# Sheet1.net
KiCad netlist of a schematic drawn in Altium Designer
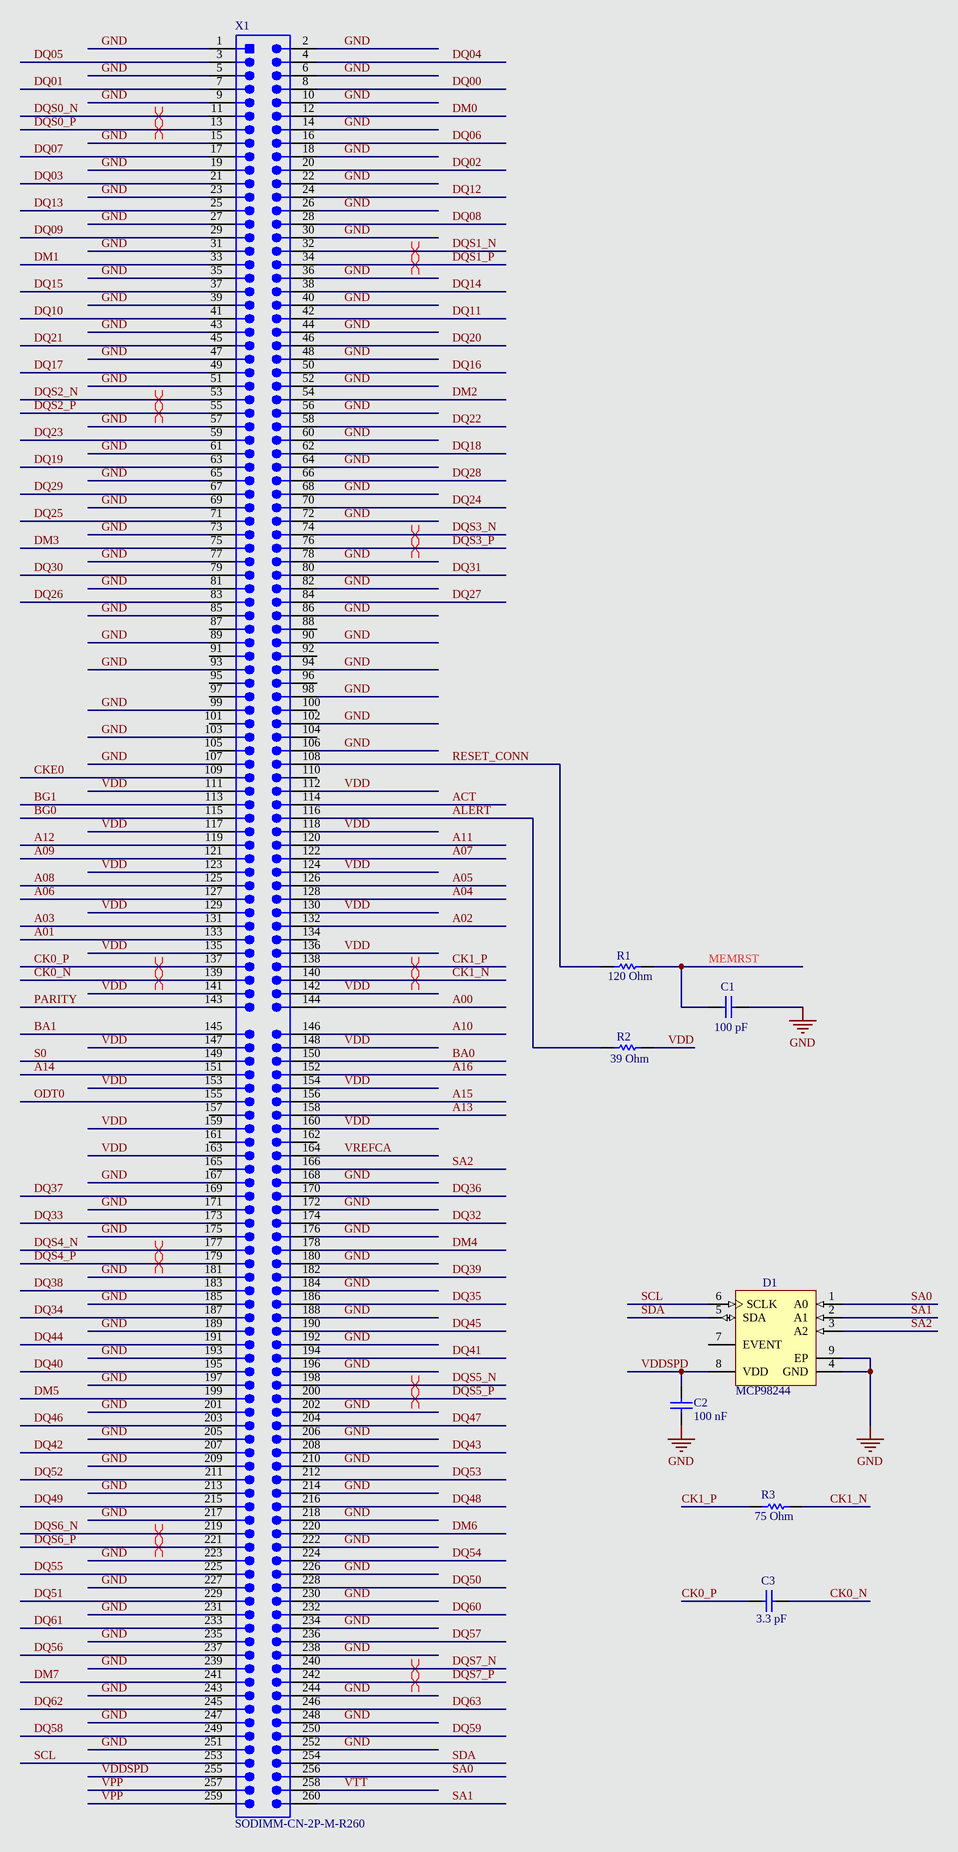
[diagram p0: Sheet1.SchDoc]

(export (version "E")
  (design (tool "Eeschema 10.0.6"))
  (components
    (comp (ref "C1")
      (value "C1005C0G1H101K050BA")
      (footprint "CAPC1005X55X10LL05")
      (description "Chip Capacitor, 100 pF, +/- 10%, 50 V, -55 to 125 degC, 0402 (1005 Metric), RoHS, Tape and Reel")
      (fields (field (name "CAPACITANCE") "100 pF") (field (name "TOLERANCE") "10%"))
      (libsource (lib "Altium Content Vault") (part "CMP-1663-00011-2"))
    )
    (comp (ref "C2")
      (value "C1005X7R1E104M")
      (footprint "CAPC1005X55X10LL05")
      (description "Chip Capacitor, 0.1 uF, +/- 20%, 25 V, -55 to 125 degC, 0402 (1005 Metric), RoHS, Tape and Reel")
      (fields (field (name "TOLERANCE") "20%") (field (name "CAPACITANCE") "100 nF"))
      (libsource (lib "Altium Content Vault") (part "CMP-1663-00009-2"))
    )
    (comp (ref "C3")
      (value "GRM1555C1H3R3CA01D")
      (footprint "CAPC1005X55X25NL5T10")
      (fields (field (name "CAPACITANCE") "3.3 pF"))
      (libsource (lib "Altium Content Vault") (part "CMP-2008-04352-2"))
    )
    (comp (ref "D1")
      (value "MCP98244")
      (footprint "MCHP-TDFN-MNY8_V")
      (libsource (lib "Altium Content Vault") (part "CMP-1721-00006-1"))
    )
    (comp (ref "R1")
      (value "RC0402JR-07120RL")
      (footprint "RESC1005X40X25ML5T10")
      (description "Chip Resistor, 120 Ohm, +/- 5%, 0.063 W, -55 to 155 degC, 0402 (1005 Metric), RoHS, Tape and Reel")
      (fields (field (name "TOLERANCE") "5%") (field (name "RESISTANCE") "120 Ohm"))
      (libsource (lib "Altium Content Vault") (part "CMP-2002-07920-2"))
    )
    (comp (ref "R2")
      (value "RC0402JR-0739RL")
      (footprint "RESC1005X40X25NL5T10")
      (description "Chip Resistor, 39 Ohm, +/- 5%, 0.063 W, -55 to 155 degC, 0402 (1005 Metric), RoHS, Tape and Reel")
      (fields (field (name "TOLERANCE") "5%") (field (name "RESISTANCE") "39 Ohm"))
      (libsource (lib "Altium Content Vault") (part "CMP-2002-07994-2"))
    )
    (comp (ref "R3")
      (value "ERJ-2GEJ750X")
      (footprint "RESC1005X40X25ML05T05")
      (description "Chip Resistor, 75 Ohm, +/- 5%, 100 mW, -55 to 155 degC, 0402 (1005 Metric), RoHS, Tape and Reel")
      (fields
        (field (name "MANUFACTURER") "Basic Passives")
        (field (name "TOLERANCE") "5%")
        (field (name "RESISTANCE") "75 Ohm")
      )
      (libsource (lib "Altium Content Vault") (part "CMP-2002-00578-3"))
    )
    (comp (ref "X1")
      (value "SODIMM-CN-2P-M-R260")
      (footprint "SODIMM-GF-2D-500-1K-S260")
      (description "Golden finger, SODIMM, Dual, Staggered, Pitch 0.5mm, 260-Position")
      (fields (field (name "PUBLISHER") "Altium"))
      (libsource (lib "Altium Content Vault") (part "CMP-0001-00005-1"))
    )
  )
  (nets
    (net (code "1") (name "/A00") (class "Default")
      (node (ref "X1") (pin "144") (pinfunction "144_144") (pintype "passive"))
    )
    (net (code "2") (name "/A01") (class "Default")
      (node (ref "X1") (pin "133") (pinfunction "133_133") (pintype "passive"))
    )
    (net (code "3") (name "/A02") (class "Default")
      (node (ref "X1") (pin "132") (pinfunction "132_132") (pintype "passive"))
    )
    (net (code "4") (name "/A03") (class "Default")
      (node (ref "X1") (pin "131") (pinfunction "131_131") (pintype "passive"))
    )
    (net (code "5") (name "/A04") (class "Default")
      (node (ref "X1") (pin "128") (pinfunction "128_128") (pintype "passive"))
    )
    (net (code "6") (name "/A05") (class "Default")
      (node (ref "X1") (pin "126") (pinfunction "126_126") (pintype "passive"))
    )
    (net (code "7") (name "/A06") (class "Default")
      (node (ref "X1") (pin "127") (pinfunction "127_127") (pintype "passive"))
    )
    (net (code "8") (name "/A07") (class "Default")
      (node (ref "X1") (pin "122") (pinfunction "122_122") (pintype "passive"))
    )
    (net (code "9") (name "/A08") (class "Default")
      (node (ref "X1") (pin "125") (pinfunction "125_125") (pintype "passive"))
    )
    (net (code "10") (name "/A09") (class "Default")
      (node (ref "X1") (pin "121") (pinfunction "121_121") (pintype "passive"))
    )
    (net (code "11") (name "/A10") (class "Default")
      (node (ref "X1") (pin "146") (pinfunction "146_146") (pintype "passive"))
    )
    (net (code "12") (name "/A11") (class "Default")
      (node (ref "X1") (pin "120") (pinfunction "120_120") (pintype "passive"))
    )
    (net (code "13") (name "/A12") (class "Default")
      (node (ref "X1") (pin "119") (pinfunction "119_119") (pintype "passive"))
    )
    (net (code "14") (name "/A13") (class "Default")
      (node (ref "X1") (pin "158") (pinfunction "158_158") (pintype "passive"))
    )
    (net (code "15") (name "/A14") (class "Default")
      (node (ref "X1") (pin "151") (pinfunction "151_151") (pintype "passive"))
    )
    (net (code "16") (name "/A15") (class "Default")
      (node (ref "X1") (pin "156") (pinfunction "156_156") (pintype "passive"))
    )
    (net (code "17") (name "/A16") (class "Default")
      (node (ref "X1") (pin "152") (pinfunction "152_152") (pintype "passive"))
    )
    (net (code "18") (name "/ACT") (class "Default")
      (node (ref "X1") (pin "114") (pinfunction "114_114") (pintype "passive"))
    )
    (net (code "19") (name "/ALERT") (class "Default")
      (node (ref "R2") (pin "1") (pinfunction "1_1") (pintype "passive"))
      (node (ref "X1") (pin "116") (pinfunction "116_116") (pintype "passive"))
    )
    (net (code "20") (name "/BA0") (class "Default")
      (node (ref "X1") (pin "150") (pinfunction "150_150") (pintype "passive"))
    )
    (net (code "21") (name "/BA1") (class "Default")
      (node (ref "X1") (pin "145") (pinfunction "145_145") (pintype "passive"))
    )
    (net (code "22") (name "/BG0") (class "Default")
      (node (ref "X1") (pin "115") (pinfunction "115_115") (pintype "passive"))
    )
    (net (code "23") (name "/BG1") (class "Default")
      (node (ref "X1") (pin "113") (pinfunction "113_113") (pintype "passive"))
    )
    (net (code "24") (name "/CK0_N") (class "Default")
      (node (ref "C3") (pin "2") (pinfunction "2_2") (pintype "passive"))
      (node (ref "X1") (pin "139") (pinfunction "139_139") (pintype "passive"))
    )
    (net (code "25") (name "/CK0_P") (class "Default")
      (node (ref "C3") (pin "1") (pinfunction "1_1") (pintype "passive"))
      (node (ref "X1") (pin "137") (pinfunction "137_137") (pintype "passive"))
    )
    (net (code "26") (name "/CK1_N") (class "Default")
      (node (ref "R3") (pin "2") (pinfunction "2_2") (pintype "passive"))
      (node (ref "X1") (pin "140") (pinfunction "140_140") (pintype "passive"))
    )
    (net (code "27") (name "/CK1_P") (class "Default")
      (node (ref "R3") (pin "1") (pinfunction "1_1") (pintype "passive"))
      (node (ref "X1") (pin "138") (pinfunction "138_138") (pintype "passive"))
    )
    (net (code "28") (name "/CKE0") (class "Default")
      (node (ref "X1") (pin "109") (pinfunction "109_109") (pintype "passive"))
    )
    (net (code "29") (name "/DM0") (class "Default")
      (node (ref "X1") (pin "12") (pinfunction "12_12") (pintype "passive"))
    )
    (net (code "30") (name "/DM1") (class "Default")
      (node (ref "X1") (pin "33") (pinfunction "33_33") (pintype "passive"))
    )
    (net (code "31") (name "/DM2") (class "Default")
      (node (ref "X1") (pin "54") (pinfunction "54_54") (pintype "passive"))
    )
    (net (code "32") (name "/DM3") (class "Default")
      (node (ref "X1") (pin "75") (pinfunction "75_75") (pintype "passive"))
    )
    (net (code "33") (name "/DM4") (class "Default")
      (node (ref "X1") (pin "178") (pinfunction "178_178") (pintype "passive"))
    )
    (net (code "34") (name "/DM5") (class "Default")
      (node (ref "X1") (pin "199") (pinfunction "199_199") (pintype "passive"))
    )
    (net (code "35") (name "/DM6") (class "Default")
      (node (ref "X1") (pin "220") (pinfunction "220_220") (pintype "passive"))
    )
    (net (code "36") (name "/DM7") (class "Default")
      (node (ref "X1") (pin "241") (pinfunction "241_241") (pintype "passive"))
    )
    (net (code "37") (name "/DQ00") (class "Default")
      (node (ref "X1") (pin "8") (pinfunction "8_8") (pintype "passive"))
    )
    (net (code "38") (name "/DQ01") (class "Default")
      (node (ref "X1") (pin "7") (pinfunction "7_7") (pintype "passive"))
    )
    (net (code "39") (name "/DQ02") (class "Default")
      (node (ref "X1") (pin "20") (pinfunction "20_20") (pintype "passive"))
    )
    (net (code "40") (name "/DQ03") (class "Default")
      (node (ref "X1") (pin "21") (pinfunction "21_21") (pintype "passive"))
    )
    (net (code "41") (name "/DQ04") (class "Default")
      (node (ref "X1") (pin "4") (pinfunction "4_4") (pintype "passive"))
    )
    (net (code "42") (name "/DQ05") (class "Default")
      (node (ref "X1") (pin "3") (pinfunction "3_3") (pintype "passive"))
    )
    (net (code "43") (name "/DQ06") (class "Default")
      (node (ref "X1") (pin "16") (pinfunction "16_16") (pintype "passive"))
    )
    (net (code "44") (name "/DQ07") (class "Default")
      (node (ref "X1") (pin "17") (pinfunction "17_17") (pintype "passive"))
    )
    (net (code "45") (name "/DQ08") (class "Default")
      (node (ref "X1") (pin "28") (pinfunction "28_28") (pintype "passive"))
    )
    (net (code "46") (name "/DQ09") (class "Default")
      (node (ref "X1") (pin "29") (pinfunction "29_29") (pintype "passive"))
    )
    (net (code "47") (name "/DQ10") (class "Default")
      (node (ref "X1") (pin "41") (pinfunction "41_41") (pintype "passive"))
    )
    (net (code "48") (name "/DQ11") (class "Default")
      (node (ref "X1") (pin "42") (pinfunction "42_42") (pintype "passive"))
    )
    (net (code "49") (name "/DQ12") (class "Default")
      (node (ref "X1") (pin "24") (pinfunction "24_24") (pintype "passive"))
    )
    (net (code "50") (name "/DQ13") (class "Default")
      (node (ref "X1") (pin "25") (pinfunction "25_25") (pintype "passive"))
    )
    (net (code "51") (name "/DQ14") (class "Default")
      (node (ref "X1") (pin "38") (pinfunction "38_38") (pintype "passive"))
    )
    (net (code "52") (name "/DQ15") (class "Default")
      (node (ref "X1") (pin "37") (pinfunction "37_37") (pintype "passive"))
    )
    (net (code "53") (name "/DQ16") (class "Default")
      (node (ref "X1") (pin "50") (pinfunction "50_50") (pintype "passive"))
    )
    (net (code "54") (name "/DQ17") (class "Default")
      (node (ref "X1") (pin "49") (pinfunction "49_49") (pintype "passive"))
    )
    (net (code "55") (name "/DQ18") (class "Default")
      (node (ref "X1") (pin "62") (pinfunction "62_62") (pintype "passive"))
    )
    (net (code "56") (name "/DQ19") (class "Default")
      (node (ref "X1") (pin "63") (pinfunction "63_63") (pintype "passive"))
    )
    (net (code "57") (name "/DQ20") (class "Default")
      (node (ref "X1") (pin "46") (pinfunction "46_46") (pintype "passive"))
    )
    (net (code "58") (name "/DQ21") (class "Default")
      (node (ref "X1") (pin "45") (pinfunction "45_45") (pintype "passive"))
    )
    (net (code "59") (name "/DQ22") (class "Default")
      (node (ref "X1") (pin "58") (pinfunction "58_58") (pintype "passive"))
    )
    (net (code "60") (name "/DQ23") (class "Default")
      (node (ref "X1") (pin "59") (pinfunction "59_59") (pintype "passive"))
    )
    (net (code "61") (name "/DQ24") (class "Default")
      (node (ref "X1") (pin "70") (pinfunction "70_70") (pintype "passive"))
    )
    (net (code "62") (name "/DQ25") (class "Default")
      (node (ref "X1") (pin "71") (pinfunction "71_71") (pintype "passive"))
    )
    (net (code "63") (name "/DQ26") (class "Default")
      (node (ref "X1") (pin "83") (pinfunction "83_83") (pintype "passive"))
    )
    (net (code "64") (name "/DQ27") (class "Default")
      (node (ref "X1") (pin "84") (pinfunction "84_84") (pintype "passive"))
    )
    (net (code "65") (name "/DQ28") (class "Default")
      (node (ref "X1") (pin "66") (pinfunction "66_66") (pintype "passive"))
    )
    (net (code "66") (name "/DQ29") (class "Default")
      (node (ref "X1") (pin "67") (pinfunction "67_67") (pintype "passive"))
    )
    (net (code "67") (name "/DQ30") (class "Default")
      (node (ref "X1") (pin "79") (pinfunction "79_79") (pintype "passive"))
    )
    (net (code "68") (name "/DQ31") (class "Default")
      (node (ref "X1") (pin "80") (pinfunction "80_80") (pintype "passive"))
    )
    (net (code "69") (name "/DQ32") (class "Default")
      (node (ref "X1") (pin "174") (pinfunction "174_174") (pintype "passive"))
    )
    (net (code "70") (name "/DQ33") (class "Default")
      (node (ref "X1") (pin "173") (pinfunction "173_173") (pintype "passive"))
    )
    (net (code "71") (name "/DQ34") (class "Default")
      (node (ref "X1") (pin "187") (pinfunction "187_187") (pintype "passive"))
    )
    (net (code "72") (name "/DQ35") (class "Default")
      (node (ref "X1") (pin "186") (pinfunction "186_186") (pintype "passive"))
    )
    (net (code "73") (name "/DQ36") (class "Default")
      (node (ref "X1") (pin "170") (pinfunction "170_170") (pintype "passive"))
    )
    (net (code "74") (name "/DQ37") (class "Default")
      (node (ref "X1") (pin "169") (pinfunction "169_169") (pintype "passive"))
    )
    (net (code "75") (name "/DQ38") (class "Default")
      (node (ref "X1") (pin "183") (pinfunction "183_183") (pintype "passive"))
    )
    (net (code "76") (name "/DQ39") (class "Default")
      (node (ref "X1") (pin "182") (pinfunction "182_182") (pintype "passive"))
    )
    (net (code "77") (name "/DQ40") (class "Default")
      (node (ref "X1") (pin "195") (pinfunction "195_195") (pintype "passive"))
    )
    (net (code "78") (name "/DQ41") (class "Default")
      (node (ref "X1") (pin "194") (pinfunction "194_194") (pintype "passive"))
    )
    (net (code "79") (name "/DQ42") (class "Default")
      (node (ref "X1") (pin "207") (pinfunction "207_207") (pintype "passive"))
    )
    (net (code "80") (name "/DQ43") (class "Default")
      (node (ref "X1") (pin "208") (pinfunction "208_208") (pintype "passive"))
    )
    (net (code "81") (name "/DQ44") (class "Default")
      (node (ref "X1") (pin "191") (pinfunction "191_191") (pintype "passive"))
    )
    (net (code "82") (name "/DQ45") (class "Default")
      (node (ref "X1") (pin "190") (pinfunction "190_190") (pintype "passive"))
    )
    (net (code "83") (name "/DQ46") (class "Default")
      (node (ref "X1") (pin "203") (pinfunction "203_203") (pintype "passive"))
    )
    (net (code "84") (name "/DQ47") (class "Default")
      (node (ref "X1") (pin "204") (pinfunction "204_204") (pintype "passive"))
    )
    (net (code "85") (name "/DQ48") (class "Default")
      (node (ref "X1") (pin "216") (pinfunction "216_216") (pintype "passive"))
    )
    (net (code "86") (name "/DQ49") (class "Default")
      (node (ref "X1") (pin "215") (pinfunction "215_215") (pintype "passive"))
    )
    (net (code "87") (name "/DQ50") (class "Default")
      (node (ref "X1") (pin "228") (pinfunction "228_228") (pintype "passive"))
    )
    (net (code "88") (name "/DQ51") (class "Default")
      (node (ref "X1") (pin "229") (pinfunction "229_229") (pintype "passive"))
    )
    (net (code "89") (name "/DQ52") (class "Default")
      (node (ref "X1") (pin "211") (pinfunction "211_211") (pintype "passive"))
    )
    (net (code "90") (name "/DQ53") (class "Default")
      (node (ref "X1") (pin "212") (pinfunction "212_212") (pintype "passive"))
    )
    (net (code "91") (name "/DQ54") (class "Default")
      (node (ref "X1") (pin "224") (pinfunction "224_224") (pintype "passive"))
    )
    (net (code "92") (name "/DQ55") (class "Default")
      (node (ref "X1") (pin "225") (pinfunction "225_225") (pintype "passive"))
    )
    (net (code "93") (name "/DQ56") (class "Default")
      (node (ref "X1") (pin "237") (pinfunction "237_237") (pintype "passive"))
    )
    (net (code "94") (name "/DQ57") (class "Default")
      (node (ref "X1") (pin "236") (pinfunction "236_236") (pintype "passive"))
    )
    (net (code "95") (name "/DQ58") (class "Default")
      (node (ref "X1") (pin "249") (pinfunction "249_249") (pintype "passive"))
    )
    (net (code "96") (name "/DQ59") (class "Default")
      (node (ref "X1") (pin "250") (pinfunction "250_250") (pintype "passive"))
    )
    (net (code "97") (name "/DQ60") (class "Default")
      (node (ref "X1") (pin "232") (pinfunction "232_232") (pintype "passive"))
    )
    (net (code "98") (name "/DQ61") (class "Default")
      (node (ref "X1") (pin "233") (pinfunction "233_233") (pintype "passive"))
    )
    (net (code "99") (name "/DQ62") (class "Default")
      (node (ref "X1") (pin "245") (pinfunction "245_245") (pintype "passive"))
    )
    (net (code "100") (name "/DQ63") (class "Default")
      (node (ref "X1") (pin "246") (pinfunction "246_246") (pintype "passive"))
    )
    (net (code "101") (name "/DQS0_N") (class "Default")
      (node (ref "X1") (pin "11") (pinfunction "11_11") (pintype "passive"))
    )
    (net (code "102") (name "/DQS0_P") (class "Default")
      (node (ref "X1") (pin "13") (pinfunction "13_13") (pintype "passive"))
    )
    (net (code "103") (name "/DQS1_N") (class "Default")
      (node (ref "X1") (pin "32") (pinfunction "32_32") (pintype "passive"))
    )
    (net (code "104") (name "/DQS1_P") (class "Default")
      (node (ref "X1") (pin "34") (pinfunction "34_34") (pintype "passive"))
    )
    (net (code "105") (name "/DQS2_N") (class "Default")
      (node (ref "X1") (pin "53") (pinfunction "53_53") (pintype "passive"))
    )
    (net (code "106") (name "/DQS2_P") (class "Default")
      (node (ref "X1") (pin "55") (pinfunction "55_55") (pintype "passive"))
    )
    (net (code "107") (name "/DQS3_N") (class "Default")
      (node (ref "X1") (pin "74") (pinfunction "74_74") (pintype "passive"))
    )
    (net (code "108") (name "/DQS3_P") (class "Default")
      (node (ref "X1") (pin "76") (pinfunction "76_76") (pintype "passive"))
    )
    (net (code "109") (name "/DQS4_N") (class "Default")
      (node (ref "X1") (pin "177") (pinfunction "177_177") (pintype "passive"))
    )
    (net (code "110") (name "/DQS4_P") (class "Default")
      (node (ref "X1") (pin "179") (pinfunction "179_179") (pintype "passive"))
    )
    (net (code "111") (name "/DQS5_N") (class "Default")
      (node (ref "X1") (pin "198") (pinfunction "198_198") (pintype "passive"))
    )
    (net (code "112") (name "/DQS5_P") (class "Default")
      (node (ref "X1") (pin "200") (pinfunction "200_200") (pintype "passive"))
    )
    (net (code "113") (name "/DQS6_N") (class "Default")
      (node (ref "X1") (pin "219") (pinfunction "219_219") (pintype "passive"))
    )
    (net (code "114") (name "/DQS6_P") (class "Default")
      (node (ref "X1") (pin "221") (pinfunction "221_221") (pintype "passive"))
    )
    (net (code "115") (name "/DQS7_N") (class "Default")
      (node (ref "X1") (pin "240") (pinfunction "240_240") (pintype "passive"))
    )
    (net (code "116") (name "/DQS7_P") (class "Default")
      (node (ref "X1") (pin "242") (pinfunction "242_242") (pintype "passive"))
    )
    (net (code "117") (name "/MEMRST") (class "Default")
      (node (ref "C1") (pin "1") (pinfunction "1_1") (pintype "passive"))
      (node (ref "R1") (pin "2") (pinfunction "2_2") (pintype "passive"))
    )
    (net (code "118") (name "/ODT0") (class "Default")
      (node (ref "X1") (pin "155") (pinfunction "155_155") (pintype "passive"))
    )
    (net (code "119") (name "/PARITY") (class "Default")
      (node (ref "X1") (pin "143") (pinfunction "143_143") (pintype "passive"))
    )
    (net (code "120") (name "/RESET_CONN") (class "Default")
      (node (ref "R1") (pin "1") (pinfunction "1_1") (pintype "passive"))
      (node (ref "X1") (pin "108") (pinfunction "108_108") (pintype "passive"))
    )
    (net (code "121") (name "/S0") (class "Default")
      (node (ref "X1") (pin "149") (pinfunction "149_149") (pintype "passive"))
    )
    (net (code "122") (name "/SA0") (class "Default")
      (node (ref "D1") (pin "1") (pinfunction "A0_1") (pintype "input"))
      (node (ref "X1") (pin "256") (pinfunction "256_256") (pintype "passive"))
    )
    (net (code "123") (name "/SA1") (class "Default")
      (node (ref "D1") (pin "2") (pinfunction "A1_2") (pintype "input"))
      (node (ref "X1") (pin "260") (pinfunction "260_260") (pintype "passive"))
    )
    (net (code "124") (name "/SA2") (class "Default")
      (node (ref "D1") (pin "3") (pinfunction "A2_3") (pintype "input"))
      (node (ref "X1") (pin "166") (pinfunction "166_166") (pintype "passive"))
    )
    (net (code "125") (name "/SCL") (class "Default")
      (node (ref "D1") (pin "6") (pinfunction "SCLK_6") (pintype "input"))
      (node (ref "X1") (pin "253") (pinfunction "253_253") (pintype "passive"))
    )
    (net (code "126") (name "/SDA") (class "Default")
      (node (ref "D1") (pin "5") (pinfunction "SDA_5") (pintype "bidirectional"))
      (node (ref "X1") (pin "254") (pinfunction "254_254") (pintype "passive"))
    )
    (net (code "127") (name "/VDD") (class "Default")
      (node (ref "R2") (pin "2") (pinfunction "2_2") (pintype "passive"))
      (node (ref "X1") (pin "111") (pinfunction "111_111") (pintype "passive"))
      (node (ref "X1") (pin "112") (pinfunction "112_112") (pintype "passive"))
      (node (ref "X1") (pin "117") (pinfunction "117_117") (pintype "passive"))
      (node (ref "X1") (pin "118") (pinfunction "118_118") (pintype "passive"))
      (node (ref "X1") (pin "123") (pinfunction "123_123") (pintype "passive"))
      (node (ref "X1") (pin "124") (pinfunction "124_124") (pintype "passive"))
      (node (ref "X1") (pin "129") (pinfunction "129_129") (pintype "passive"))
      (node (ref "X1") (pin "130") (pinfunction "130_130") (pintype "passive"))
      (node (ref "X1") (pin "135") (pinfunction "135_135") (pintype "passive"))
      (node (ref "X1") (pin "136") (pinfunction "136_136") (pintype "passive"))
      (node (ref "X1") (pin "141") (pinfunction "141_141") (pintype "passive"))
      (node (ref "X1") (pin "142") (pinfunction "142_142") (pintype "passive"))
      (node (ref "X1") (pin "147") (pinfunction "147_147") (pintype "passive"))
      (node (ref "X1") (pin "148") (pinfunction "148_148") (pintype "passive"))
      (node (ref "X1") (pin "153") (pinfunction "153_153") (pintype "passive"))
      (node (ref "X1") (pin "154") (pinfunction "154_154") (pintype "passive"))
      (node (ref "X1") (pin "159") (pinfunction "159_159") (pintype "passive"))
      (node (ref "X1") (pin "160") (pinfunction "160_160") (pintype "passive"))
      (node (ref "X1") (pin "163") (pinfunction "163_163") (pintype "passive"))
    )
    (net (code "128") (name "/VDDSPD") (class "Default")
      (node (ref "C2") (pin "2") (pinfunction "2_2") (pintype "passive"))
      (node (ref "D1") (pin "8") (pinfunction "VDD_8") (pintype "power_in"))
      (node (ref "X1") (pin "255") (pinfunction "255_255") (pintype "passive"))
    )
    (net (code "129") (name "/VPP") (class "Default")
      (node (ref "X1") (pin "257") (pinfunction "257_257") (pintype "passive"))
      (node (ref "X1") (pin "259") (pinfunction "259_259") (pintype "passive"))
    )
    (net (code "130") (name "/VREFCA") (class "Default")
      (node (ref "X1") (pin "164") (pinfunction "164_164") (pintype "passive"))
    )
    (net (code "131") (name "/VTT") (class "Default")
      (node (ref "X1") (pin "258") (pinfunction "258_258") (pintype "passive"))
    )
    (net (code "132") (name "GND") (class "Default")
      (node (ref "C1") (pin "2") (pinfunction "2_2") (pintype "passive"))
      (node (ref "C2") (pin "1") (pinfunction "1_1") (pintype "passive"))
      (node (ref "D1") (pin "4") (pinfunction "GND_4") (pintype "power_in"))
      (node (ref "D1") (pin "9") (pinfunction "EP_9") (pintype "power_in"))
      (node (ref "X1") (pin "1") (pinfunction "1_1") (pintype "passive"))
      (node (ref "X1") (pin "10") (pinfunction "10_10") (pintype "passive"))
      (node (ref "X1") (pin "102") (pinfunction "102_102") (pintype "passive"))
      (node (ref "X1") (pin "103") (pinfunction "103_103") (pintype "passive"))
      (node (ref "X1") (pin "106") (pinfunction "106_106") (pintype "passive"))
      (node (ref "X1") (pin "107") (pinfunction "107_107") (pintype "passive"))
      (node (ref "X1") (pin "14") (pinfunction "14_14") (pintype "passive"))
      (node (ref "X1") (pin "15") (pinfunction "15_15") (pintype "passive"))
      (node (ref "X1") (pin "167") (pinfunction "167_167") (pintype "passive"))
      (node (ref "X1") (pin "168") (pinfunction "168_168") (pintype "passive"))
      (node (ref "X1") (pin "171") (pinfunction "171_171") (pintype "passive"))
      (node (ref "X1") (pin "172") (pinfunction "172_172") (pintype "passive"))
      (node (ref "X1") (pin "175") (pinfunction "175_175") (pintype "passive"))
      (node (ref "X1") (pin "176") (pinfunction "176_176") (pintype "passive"))
      (node (ref "X1") (pin "18") (pinfunction "18_18") (pintype "passive"))
      (node (ref "X1") (pin "180") (pinfunction "180_180") (pintype "passive"))
      (node (ref "X1") (pin "181") (pinfunction "181_181") (pintype "passive"))
      (node (ref "X1") (pin "184") (pinfunction "184_184") (pintype "passive"))
      (node (ref "X1") (pin "185") (pinfunction "185_185") (pintype "passive"))
      (node (ref "X1") (pin "188") (pinfunction "188_188") (pintype "passive"))
      (node (ref "X1") (pin "189") (pinfunction "189_189") (pintype "passive"))
      (node (ref "X1") (pin "19") (pinfunction "19_19") (pintype "passive"))
      (node (ref "X1") (pin "192") (pinfunction "192_192") (pintype "passive"))
      (node (ref "X1") (pin "193") (pinfunction "193_193") (pintype "passive"))
      (node (ref "X1") (pin "196") (pinfunction "196_196") (pintype "passive"))
      (node (ref "X1") (pin "197") (pinfunction "197_197") (pintype "passive"))
      (node (ref "X1") (pin "2") (pinfunction "2_2") (pintype "passive"))
      (node (ref "X1") (pin "201") (pinfunction "201_201") (pintype "passive"))
      (node (ref "X1") (pin "202") (pinfunction "202_202") (pintype "passive"))
      (node (ref "X1") (pin "205") (pinfunction "205_205") (pintype "passive"))
      (node (ref "X1") (pin "206") (pinfunction "206_206") (pintype "passive"))
      (node (ref "X1") (pin "209") (pinfunction "209_209") (pintype "passive"))
      (node (ref "X1") (pin "210") (pinfunction "210_210") (pintype "passive"))
      (node (ref "X1") (pin "213") (pinfunction "213_213") (pintype "passive"))
      (node (ref "X1") (pin "214") (pinfunction "214_214") (pintype "passive"))
      (node (ref "X1") (pin "217") (pinfunction "217_217") (pintype "passive"))
      (node (ref "X1") (pin "218") (pinfunction "218_218") (pintype "passive"))
      (node (ref "X1") (pin "22") (pinfunction "22_22") (pintype "passive"))
      (node (ref "X1") (pin "222") (pinfunction "222_222") (pintype "passive"))
      (node (ref "X1") (pin "223") (pinfunction "223_223") (pintype "passive"))
      (node (ref "X1") (pin "226") (pinfunction "226_226") (pintype "passive"))
      (node (ref "X1") (pin "227") (pinfunction "227_227") (pintype "passive"))
      (node (ref "X1") (pin "23") (pinfunction "23_23") (pintype "passive"))
      (node (ref "X1") (pin "230") (pinfunction "230_230") (pintype "passive"))
      (node (ref "X1") (pin "231") (pinfunction "231_231") (pintype "passive"))
      (node (ref "X1") (pin "234") (pinfunction "234_234") (pintype "passive"))
      (node (ref "X1") (pin "235") (pinfunction "235_235") (pintype "passive"))
      (node (ref "X1") (pin "238") (pinfunction "238_238") (pintype "passive"))
      (node (ref "X1") (pin "239") (pinfunction "239_239") (pintype "passive"))
      (node (ref "X1") (pin "243") (pinfunction "243_243") (pintype "passive"))
      (node (ref "X1") (pin "244") (pinfunction "244_244") (pintype "passive"))
      (node (ref "X1") (pin "247") (pinfunction "247_247") (pintype "passive"))
      (node (ref "X1") (pin "248") (pinfunction "248_248") (pintype "passive"))
      (node (ref "X1") (pin "251") (pinfunction "251_251") (pintype "passive"))
      (node (ref "X1") (pin "252") (pinfunction "252_252") (pintype "passive"))
      (node (ref "X1") (pin "26") (pinfunction "26_26") (pintype "passive"))
      (node (ref "X1") (pin "27") (pinfunction "27_27") (pintype "passive"))
      (node (ref "X1") (pin "30") (pinfunction "30_30") (pintype "passive"))
      (node (ref "X1") (pin "31") (pinfunction "31_31") (pintype "passive"))
      (node (ref "X1") (pin "35") (pinfunction "35_35") (pintype "passive"))
      (node (ref "X1") (pin "36") (pinfunction "36_36") (pintype "passive"))
      (node (ref "X1") (pin "39") (pinfunction "39_39") (pintype "passive"))
      (node (ref "X1") (pin "40") (pinfunction "40_40") (pintype "passive"))
      (node (ref "X1") (pin "43") (pinfunction "43_43") (pintype "passive"))
      (node (ref "X1") (pin "44") (pinfunction "44_44") (pintype "passive"))
      (node (ref "X1") (pin "47") (pinfunction "47_47") (pintype "passive"))
      (node (ref "X1") (pin "48") (pinfunction "48_48") (pintype "passive"))
      (node (ref "X1") (pin "5") (pinfunction "5_5") (pintype "passive"))
      (node (ref "X1") (pin "51") (pinfunction "51_51") (pintype "passive"))
      (node (ref "X1") (pin "52") (pinfunction "52_52") (pintype "passive"))
      (node (ref "X1") (pin "56") (pinfunction "56_56") (pintype "passive"))
      (node (ref "X1") (pin "57") (pinfunction "57_57") (pintype "passive"))
      (node (ref "X1") (pin "6") (pinfunction "6_6") (pintype "passive"))
      (node (ref "X1") (pin "60") (pinfunction "60_60") (pintype "passive"))
      (node (ref "X1") (pin "61") (pinfunction "61_61") (pintype "passive"))
      (node (ref "X1") (pin "64") (pinfunction "64_64") (pintype "passive"))
      (node (ref "X1") (pin "65") (pinfunction "65_65") (pintype "passive"))
      (node (ref "X1") (pin "68") (pinfunction "68_68") (pintype "passive"))
      (node (ref "X1") (pin "69") (pinfunction "69_69") (pintype "passive"))
      (node (ref "X1") (pin "72") (pinfunction "72_72") (pintype "passive"))
      (node (ref "X1") (pin "73") (pinfunction "73_73") (pintype "passive"))
      (node (ref "X1") (pin "77") (pinfunction "77_77") (pintype "passive"))
      (node (ref "X1") (pin "78") (pinfunction "78_78") (pintype "passive"))
      (node (ref "X1") (pin "81") (pinfunction "81_81") (pintype "passive"))
      (node (ref "X1") (pin "82") (pinfunction "82_82") (pintype "passive"))
      (node (ref "X1") (pin "85") (pinfunction "85_85") (pintype "passive"))
      (node (ref "X1") (pin "86") (pinfunction "86_86") (pintype "passive"))
      (node (ref "X1") (pin "89") (pinfunction "89_89") (pintype "passive"))
      (node (ref "X1") (pin "9") (pinfunction "9_9") (pintype "passive"))
      (node (ref "X1") (pin "90") (pinfunction "90_90") (pintype "passive"))
      (node (ref "X1") (pin "93") (pinfunction "93_93") (pintype "passive"))
      (node (ref "X1") (pin "94") (pinfunction "94_94") (pintype "passive"))
      (node (ref "X1") (pin "98") (pinfunction "98_98") (pintype "passive"))
      (node (ref "X1") (pin "99") (pinfunction "99_99") (pintype "passive"))
    )
    (net (code "133") (name "unconnected-(D1-EVENT-Pad7)") (class "Default")
      (node (ref "D1") (pin "7") (pinfunction "EVENT_7") (pintype "open_collector"))
    )
    (net (code "134") (name "unconnected-(X1-Pad87)") (class "Default")
      (node (ref "X1") (pin "87") (pinfunction "87_87") (pintype "passive"))
    )
    (net (code "135") (name "unconnected-(X1-Pad88)") (class "Default")
      (node (ref "X1") (pin "88") (pinfunction "88_88") (pintype "passive"))
    )
    (net (code "136") (name "unconnected-(X1-Pad91)") (class "Default")
      (node (ref "X1") (pin "91") (pinfunction "91_91") (pintype "passive"))
    )
    (net (code "137") (name "unconnected-(X1-Pad92)") (class "Default")
      (node (ref "X1") (pin "92") (pinfunction "92_92") (pintype "passive"))
    )
    (net (code "138") (name "unconnected-(X1-Pad95)") (class "Default")
      (node (ref "X1") (pin "95") (pinfunction "95_95") (pintype "passive"))
    )
    (net (code "139") (name "unconnected-(X1-Pad96)") (class "Default")
      (node (ref "X1") (pin "96") (pinfunction "96_96") (pintype "passive"))
    )
    (net (code "140") (name "unconnected-(X1-Pad97)") (class "Default")
      (node (ref "X1") (pin "97") (pinfunction "97_97") (pintype "passive"))
    )
    (net (code "141") (name "unconnected-(X1-Pad100)") (class "Default")
      (node (ref "X1") (pin "100") (pinfunction "100_100") (pintype "passive"))
    )
    (net (code "142") (name "unconnected-(X1-Pad101)") (class "Default")
      (node (ref "X1") (pin "101") (pinfunction "101_101") (pintype "passive"))
    )
    (net (code "143") (name "unconnected-(X1-Pad104)") (class "Default")
      (node (ref "X1") (pin "104") (pinfunction "104_104") (pintype "passive"))
    )
    (net (code "144") (name "unconnected-(X1-Pad105)") (class "Default")
      (node (ref "X1") (pin "105") (pinfunction "105_105") (pintype "passive"))
    )
    (net (code "145") (name "unconnected-(X1-Pad110)") (class "Default")
      (node (ref "X1") (pin "110") (pinfunction "110_110") (pintype "passive"))
    )
    (net (code "146") (name "unconnected-(X1-Pad134)") (class "Default")
      (node (ref "X1") (pin "134") (pinfunction "134_134") (pintype "passive"))
    )
    (net (code "147") (name "unconnected-(X1-Pad157)") (class "Default")
      (node (ref "X1") (pin "157") (pinfunction "157_157") (pintype "passive"))
    )
    (net (code "148") (name "unconnected-(X1-Pad161)") (class "Default")
      (node (ref "X1") (pin "161") (pinfunction "161_161") (pintype "passive"))
    )
    (net (code "149") (name "unconnected-(X1-Pad162)") (class "Default")
      (node (ref "X1") (pin "162") (pinfunction "162_162") (pintype "passive"))
    )
    (net (code "150") (name "unconnected-(X1-Pad165)") (class "Default")
      (node (ref "X1") (pin "165") (pinfunction "165_165") (pintype "passive"))
    )
  )
)
